# COMMUNICATION.net
KiCad netlist of a schematic drawn in Altium Designer
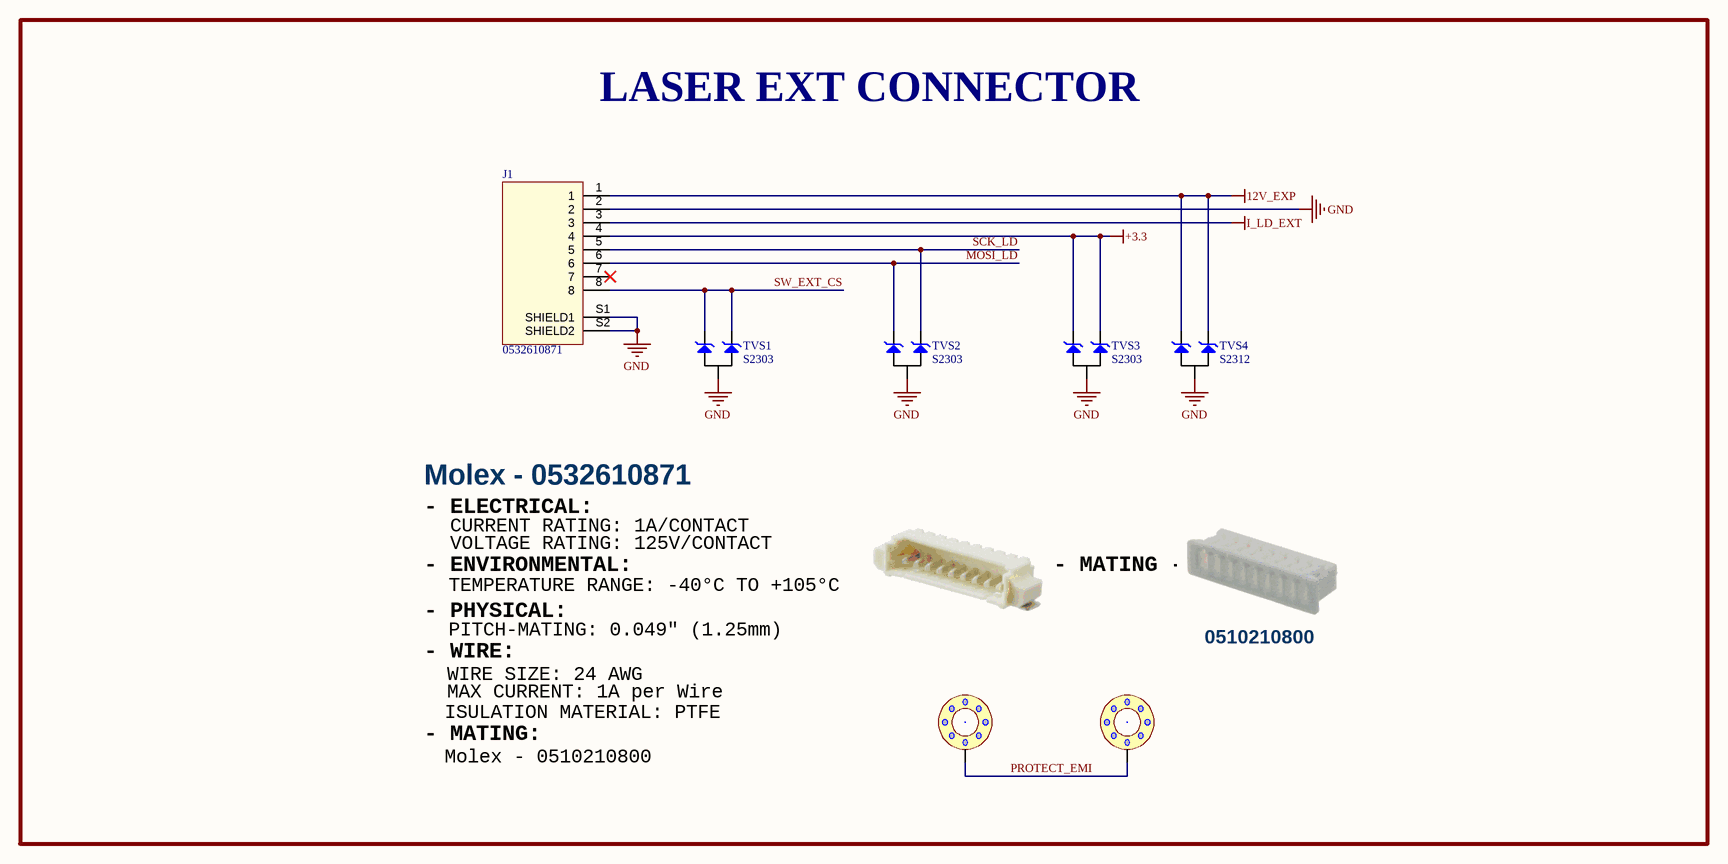
[diagram p0: COMMUNICATION.SchDoc]

(export (version "E")
  (design (tool "Eeschema 10.0.6"))
  (components
    (comp (ref "Hole1") (value "Hole") (footprint "Hole space") (libsource (lib "Library") (part "Hole")))
    (comp (ref "Hole2") (value "Hole") (footprint "Hole space") (libsource (lib "Library") (part "Hole")))
    (comp (ref "J1")
      (value "0532610871")
      (footprint "0532610871")
      (description "CONN HEADER SMD R/A 8POS 1.25MM")
      (libsource (lib "Library") (part "Header8 - Shield"))
    )
    (comp (ref "TVS1")
      (value "S2303")
      (footprint "SOT23-123")
      (description "TVS DIODE 3.3VWM 8VC SOT233")
      (libsource (lib "Library") (part "S2303"))
    )
    (comp (ref "TVS2")
      (value "S2303")
      (footprint "SOT23-123")
      (description "TVS DIODE 3.3VWM 8VC SOT233")
      (libsource (lib "Library") (part "S2303"))
    )
    (comp (ref "TVS3")
      (value "S2303")
      (footprint "SOT23-123")
      (description "TVS DIODE 3.3VWM 8VC SOT233")
      (libsource (lib "Library") (part "S2303"))
    )
    (comp (ref "TVS4")
      (value "S2312")
      (footprint "SOT23-123")
      (description "TVS DIODE 12VWM 19VC SOT233")
      (libsource (lib "Library") (part "S2315"))
    )
  )
  (nets
    (net (code "1") (name "+3.3") (class "Default")
      (node (ref "J1") (pin "4") (pinfunction "4_4") (pintype "passive"))
      (node (ref "TVS3") (pin "1") (pintype "passive"))
      (node (ref "TVS3") (pin "3") (pintype "passive"))
    )
    (net (code "2") (name "/MOSI_LD") (class "Default")
      (node (ref "J1") (pin "6") (pinfunction "6_6") (pintype "passive"))
      (node (ref "TVS2") (pin "3") (pintype "passive"))
    )
    (net (code "3") (name "/PROTECT_EMI") (class "Default")
      (node (ref "Hole1") (pin "1") (pinfunction "1_1") (pintype "passive"))
      (node (ref "Hole2") (pin "1") (pinfunction "1_1") (pintype "passive"))
    )
    (net (code "4") (name "/SCK_LD") (class "Default")
      (node (ref "J1") (pin "5") (pinfunction "5_5") (pintype "passive"))
      (node (ref "TVS2") (pin "1") (pintype "passive"))
    )
    (net (code "5") (name "/SW_EXT_CS") (class "Default")
      (node (ref "J1") (pin "8") (pinfunction "8_8") (pintype "passive"))
      (node (ref "TVS1") (pin "1") (pintype "passive"))
      (node (ref "TVS1") (pin "3") (pintype "passive"))
    )
    (net (code "6") (name "12V_EXP") (class "Default")
      (node (ref "J1") (pin "1") (pinfunction "1_1") (pintype "passive"))
      (node (ref "TVS4") (pin "1") (pintype "passive"))
      (node (ref "TVS4") (pin "3") (pintype "passive"))
    )
    (net (code "7") (name "GND") (class "Default")
      (node (ref "J1") (pin "2") (pinfunction "2_2") (pintype "passive"))
      (node (ref "J1") (pin "S1") (pinfunction "SHIELD1_S1") (pintype "passive"))
      (node (ref "J1") (pin "S2") (pinfunction "SHIELD2_S2") (pintype "passive"))
      (node (ref "TVS1") (pin "2") (pintype "passive"))
      (node (ref "TVS2") (pin "2") (pintype "passive"))
      (node (ref "TVS3") (pin "2") (pintype "passive"))
      (node (ref "TVS4") (pin "2") (pintype "passive"))
    )
    (net (code "8") (name "I_LD_EXT") (class "Default")
      (node (ref "J1") (pin "3") (pinfunction "3_3") (pintype "passive"))
    )
    (net (code "9") (name "unconnected-(J1-Pad7)") (class "Default")
      (node (ref "J1") (pin "7") (pinfunction "7_7") (pintype "passive+no_connect"))
    )
  )
)
